# Macropad_v19.net
KiCad netlist of a schematic drawn in EAGLE
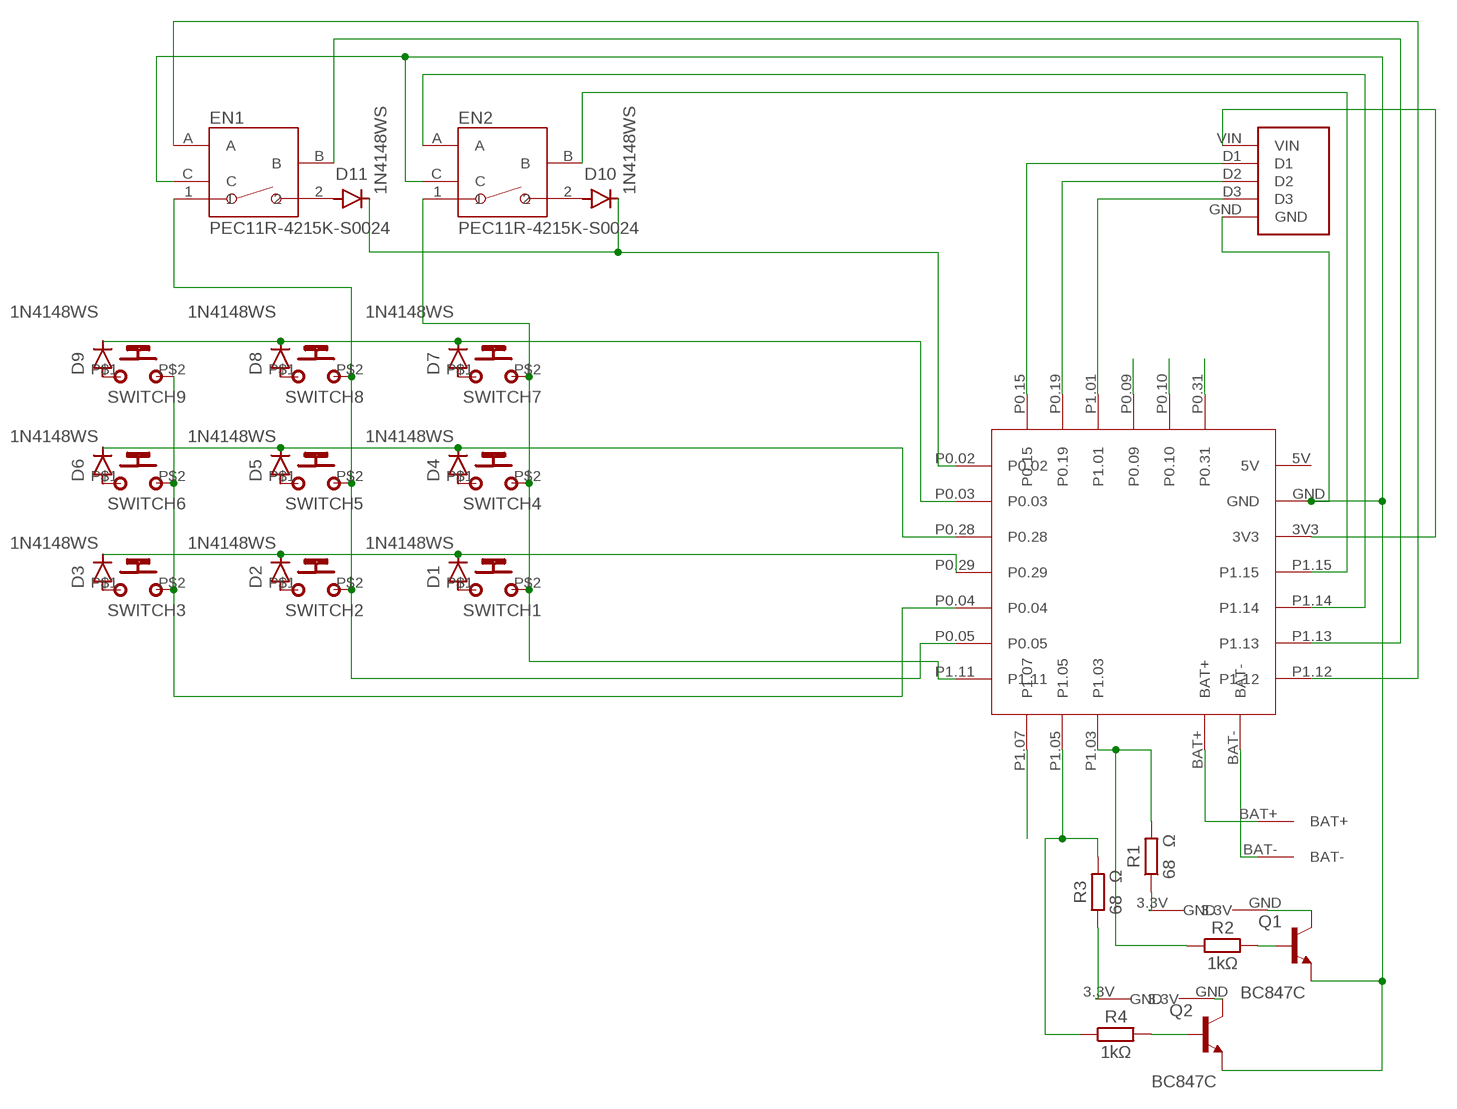
[diagram p0: schematic, sheet 1]

(export (version "E")
  (design (tool "Eeschema 10.0.6"))
  (components
    (comp (ref "D1")
      (value "1N4148WS")
      (footprint "eagle-import:SOD-323")
      (fields
        (field (name "DIGIKEY_PART_NUMBER") "1N4148WSFSTR-ND")
        (field (name "MANUFACTURER") "Diodes Incorporated")
        (field (name "CREATED_BY") "PCBLayout.com")
      )
      (libsource (lib "eagle-import") (part "1N4148WS"))
    )
    (comp (ref "D2")
      (value "1N4148WS")
      (footprint "eagle-import:SOD-323")
      (fields
        (field (name "DIGIKEY_PART_NUMBER") "1N4148WSFSTR-ND")
        (field (name "MANUFACTURER") "Diodes Incorporated")
        (field (name "CREATED_BY") "PCBLayout.com")
      )
      (libsource (lib "eagle-import") (part "1N4148WS"))
    )
    (comp (ref "D3")
      (value "1N4148WS")
      (footprint "eagle-import:SOD-323")
      (fields
        (field (name "DIGIKEY_PART_NUMBER") "1N4148WSFSTR-ND")
        (field (name "MANUFACTURER") "Diodes Incorporated")
        (field (name "CREATED_BY") "PCBLayout.com")
      )
      (libsource (lib "eagle-import") (part "1N4148WS"))
    )
    (comp (ref "D4")
      (value "1N4148WS")
      (footprint "eagle-import:SOD-323")
      (fields
        (field (name "DIGIKEY_PART_NUMBER") "1N4148WSFSTR-ND")
        (field (name "MANUFACTURER") "Diodes Incorporated")
        (field (name "CREATED_BY") "PCBLayout.com")
      )
      (libsource (lib "eagle-import") (part "1N4148WS"))
    )
    (comp (ref "D5")
      (value "1N4148WS")
      (footprint "eagle-import:SOD-323")
      (fields
        (field (name "DIGIKEY_PART_NUMBER") "1N4148WSFSTR-ND")
        (field (name "MANUFACTURER") "Diodes Incorporated")
        (field (name "CREATED_BY") "PCBLayout.com")
      )
      (libsource (lib "eagle-import") (part "1N4148WS"))
    )
    (comp (ref "D6")
      (value "1N4148WS")
      (footprint "eagle-import:SOD-323")
      (fields
        (field (name "DIGIKEY_PART_NUMBER") "1N4148WSFSTR-ND")
        (field (name "MANUFACTURER") "Diodes Incorporated")
        (field (name "CREATED_BY") "PCBLayout.com")
      )
      (libsource (lib "eagle-import") (part "1N4148WS"))
    )
    (comp (ref "D7")
      (value "1N4148WS")
      (footprint "eagle-import:SOD-323")
      (fields
        (field (name "DIGIKEY_PART_NUMBER") "1N4148WSFSTR-ND")
        (field (name "MANUFACTURER") "Diodes Incorporated")
        (field (name "CREATED_BY") "PCBLayout.com")
      )
      (libsource (lib "eagle-import") (part "1N4148WS"))
    )
    (comp (ref "D8")
      (value "1N4148WS")
      (footprint "eagle-import:SOD-323")
      (fields
        (field (name "DIGIKEY_PART_NUMBER") "1N4148WSFSTR-ND")
        (field (name "MANUFACTURER") "Diodes Incorporated")
        (field (name "CREATED_BY") "PCBLayout.com")
      )
      (libsource (lib "eagle-import") (part "1N4148WS"))
    )
    (comp (ref "D9")
      (value "1N4148WS")
      (footprint "eagle-import:SOD-323")
      (fields
        (field (name "DIGIKEY_PART_NUMBER") "1N4148WSFSTR-ND")
        (field (name "MANUFACTURER") "Diodes Incorporated")
        (field (name "CREATED_BY") "PCBLayout.com")
      )
      (libsource (lib "eagle-import") (part "1N4148WS"))
    )
    (comp (ref "D10")
      (value "1N4148WS")
      (footprint "eagle-import:SOD-323")
      (fields
        (field (name "DIGIKEY_PART_NUMBER") "1N4148WSFSTR-ND")
        (field (name "MANUFACTURER") "Diodes Incorporated")
        (field (name "CREATED_BY") "PCBLayout.com")
      )
      (libsource (lib "eagle-import") (part "1N4148WS"))
    )
    (comp (ref "D11")
      (value "1N4148WS")
      (footprint "eagle-import:SOD-323")
      (fields
        (field (name "DIGIKEY_PART_NUMBER") "1N4148WSFSTR-ND")
        (field (name "MANUFACTURER") "Diodes Incorporated")
        (field (name "CREATED_BY") "PCBLayout.com")
      )
      (libsource (lib "eagle-import") (part "1N4148WS"))
    )
    (comp (ref "EN1")
      (value "PEC11R-4215K-S0024")
      (footprint "eagle-import:PEC11R-4215K-S0024")
      (fields
        (field (name "DIGIKEY_PARTNO") "PEC11R-4215K-S0024-ND")
        (field (name "MANUFACTURER") "Bourns Inc.")
        (field (name "CREATED_BY") "PCBLayout.com")
      )
      (libsource (lib "eagle-import") (part "PEC11R-4215K-S0024"))
    )
    (comp (ref "EN2")
      (value "PEC11R-4215K-S0024")
      (footprint "eagle-import:PEC11R-4215K-S0024")
      (fields
        (field (name "DIGIKEY_PARTNO") "PEC11R-4215K-S0024-ND")
        (field (name "MANUFACTURER") "Bourns Inc.")
        (field (name "CREATED_BY") "PCBLayout.com")
      )
      (libsource (lib "eagle-import") (part "PEC11R-4215K-S0024"))
    )
    (comp (ref "Q1")
      (value "BC847C")
      (footprint "eagle-import:TRANS_BC847C")
      (fields (field (name "MF") "Diotec Semiconductor"))
      (libsource (lib "eagle-import") (part "BC847C"))
    )
    (comp (ref "Q2")
      (value "BC847C")
      (footprint "eagle-import:TRANS_BC847C")
      (fields (field (name "MF") "Diotec Semiconductor"))
      (libsource (lib "eagle-import") (part "BC847C"))
    )
    (comp (ref "R1")
      (value "68 Ω")
      (footprint "eagle-import:RESC1005X40")
      (libsource (lib "eagle-import") (part "RCHIP-0402(1005-METRIC)_"))
    )
    (comp (ref "R2")
      (value "1kΩ")
      (footprint "eagle-import:RESC1005X40")
      (libsource (lib "eagle-import") (part "RCHIP-0402(1005-METRIC)_"))
    )
    (comp (ref "R3")
      (value "68 Ω")
      (footprint "eagle-import:RESC1005X40")
      (libsource (lib "eagle-import") (part "RCHIP-0402(1005-METRIC)_"))
    )
    (comp (ref "R4")
      (value "1kΩ")
      (footprint "eagle-import:RESC1005X40")
      (libsource (lib "eagle-import") (part "RCHIP-0402(1005-METRIC)_"))
    )
    (comp (ref "SWITCH1")
      (value "MX1A-11NN")
      (footprint "eagle-import:CHERRY_MX1A-11NN_SWITCH")
      (fields (field (name "MF") "Cherry") (field (name "MP") "MX1A11NN"))
      (libsource (lib "eagle-import") (part "MX1A-11NN"))
    )
    (comp (ref "SWITCH2")
      (value "MX1A-11NN")
      (footprint "eagle-import:CHERRY_MX1A-11NN_SWITCH")
      (fields (field (name "MF") "Cherry") (field (name "MP") "MX1A11NN"))
      (libsource (lib "eagle-import") (part "MX1A-11NN"))
    )
    (comp (ref "SWITCH3")
      (value "MX1A-11NN")
      (footprint "eagle-import:CHERRY_MX1A-11NN_SWITCH")
      (fields (field (name "MF") "Cherry") (field (name "MP") "MX1A11NN"))
      (libsource (lib "eagle-import") (part "MX1A-11NN"))
    )
    (comp (ref "SWITCH4")
      (value "MX1A-11NN")
      (footprint "eagle-import:CHERRY_MX1A-11NN_SWITCH")
      (fields (field (name "MF") "Cherry") (field (name "MP") "MX1A11NN"))
      (libsource (lib "eagle-import") (part "MX1A-11NN"))
    )
    (comp (ref "SWITCH5")
      (value "MX1A-11NN")
      (footprint "eagle-import:CHERRY_MX1A-11NN_SWITCH")
      (fields (field (name "MF") "Cherry") (field (name "MP") "MX1A11NN"))
      (libsource (lib "eagle-import") (part "MX1A-11NN"))
    )
    (comp (ref "SWITCH6")
      (value "MX1A-11NN")
      (footprint "eagle-import:CHERRY_MX1A-11NN_SWITCH")
      (fields (field (name "MF") "Cherry") (field (name "MP") "MX1A11NN"))
      (libsource (lib "eagle-import") (part "MX1A-11NN"))
    )
    (comp (ref "SWITCH7")
      (value "MX1A-11NN")
      (footprint "eagle-import:CHERRY_MX1A-11NN_SWITCH")
      (fields (field (name "MF") "Cherry") (field (name "MP") "MX1A11NN"))
      (libsource (lib "eagle-import") (part "MX1A-11NN"))
    )
    (comp (ref "SWITCH8")
      (value "MX1A-11NN")
      (footprint "eagle-import:CHERRY_MX1A-11NN_SWITCH")
      (fields (field (name "MF") "Cherry") (field (name "MP") "MX1A11NN"))
      (libsource (lib "eagle-import") (part "MX1A-11NN"))
    )
    (comp (ref "SWITCH9")
      (value "MX1A-11NN")
      (footprint "eagle-import:CHERRY_MX1A-11NN_SWITCH")
      (fields (field (name "MF") "Cherry") (field (name "MP") "MX1A11NN"))
      (libsource (lib "eagle-import") (part "MX1A-11NN"))
    )
    (comp (ref "U$1")
      (value "JST-PH2.0MM")
      (footprint "eagle-import:JST-PH2.0MM")
      (libsource (lib "eagle-import") (part "JST-PH2.0MM"))
    )
    (comp (ref "U$2")
      (value "5-PIN-POGO-CONNECTOR")
      (footprint "eagle-import:5-PIN-THROUGHHOLE")
      (libsource (lib "eagle-import") (part "5-PIN-POGO-CONNECTOR"))
    )
    (comp (ref "U$3")
      (value "LED-THROUGHHOLE")
      (footprint "eagle-import:LED")
      (libsource (lib "eagle-import") (part "LED-THROUGHHOLE"))
    )
    (comp (ref "U$4")
      (value "LED-THROUGHHOLE")
      (footprint "eagle-import:LED")
      (libsource (lib "eagle-import") (part "LED-THROUGHHOLE"))
    )
    (comp (ref "XIAO_NRF52840_PLUS1")
      (value "XIAO_NRF52840_PLUS")
      (footprint "eagle-import:XIAO-NRF52840-PLUS-SMD")
      (libsource (lib "eagle-import") (part "XIAO_NRF52840_PLUS"))
    )
  )
  (nets
    (net (code "1") (name "/5V") (class "Default")
      (node (ref "XIAO_NRF52840_PLUS1") (pin "5V") (pinfunction "5V_5V") (pintype "power_in"))
    )
    (net (code "2") (name "Net-(D1-PadC)") (class "Default")
      (node (ref "D1") (pin "C") (pinfunction "C_C") (pintype "passive"))
      (node (ref "D2") (pin "C") (pinfunction "C_C") (pintype "passive"))
      (node (ref "D3") (pin "C") (pinfunction "C_C") (pintype "passive"))
      (node (ref "XIAO_NRF52840_PLUS1") (pin "P0.29") (pinfunction "P0.29_P0.29") (pintype "bidirectional"))
    )
    (net (code "3") (name "Net-(D4-PadC)") (class "Default")
      (node (ref "D4") (pin "C") (pinfunction "C_C") (pintype "passive"))
      (node (ref "D5") (pin "C") (pinfunction "C_C") (pintype "passive"))
      (node (ref "D6") (pin "C") (pinfunction "C_C") (pintype "passive"))
      (node (ref "XIAO_NRF52840_PLUS1") (pin "P0.28") (pinfunction "P0.28_P0.28") (pintype "bidirectional"))
    )
    (net (code "4") (name "Net-(D7-PadC)") (class "Default")
      (node (ref "D7") (pin "C") (pinfunction "C_C") (pintype "passive"))
      (node (ref "D8") (pin "C") (pinfunction "C_C") (pintype "passive"))
      (node (ref "D9") (pin "C") (pinfunction "C_C") (pintype "passive"))
      (node (ref "XIAO_NRF52840_PLUS1") (pin "P0.03") (pinfunction "P0.03_P0.03") (pintype "bidirectional"))
    )
    (net (code "5") (name "Net-(D10-PadA)") (class "Default")
      (node (ref "D10") (pin "A") (pinfunction "A_A") (pintype "passive"))
      (node (ref "EN2") (pin "2") (pinfunction "2_2") (pintype "passive"))
    )
    (net (code "6") (name "Net-(D10-PadC)") (class "Default")
      (node (ref "D10") (pin "C") (pinfunction "C_C") (pintype "passive"))
      (node (ref "D11") (pin "C") (pinfunction "C_C") (pintype "passive"))
      (node (ref "XIAO_NRF52840_PLUS1") (pin "P0.02") (pinfunction "P0.02_P0.02") (pintype "bidirectional"))
    )
    (net (code "7") (name "Net-(D11-PadA)") (class "Default")
      (node (ref "D11") (pin "A") (pinfunction "A_A") (pintype "passive"))
      (node (ref "EN1") (pin "2") (pinfunction "2_2") (pintype "passive"))
    )
    (net (code "8") (name "Net-(EN1-PadA)") (class "Default")
      (node (ref "EN1") (pin "A") (pinfunction "A_A") (pintype "passive"))
      (node (ref "XIAO_NRF52840_PLUS1") (pin "P1.12") (pinfunction "P1.12_P1.12") (pintype "bidirectional"))
    )
    (net (code "9") (name "Net-(EN1-PadB)") (class "Default")
      (node (ref "EN1") (pin "B") (pinfunction "B_B") (pintype "passive"))
      (node (ref "XIAO_NRF52840_PLUS1") (pin "P1.13") (pinfunction "P1.13_P1.13") (pintype "bidirectional"))
    )
    (net (code "10") (name "Net-(EN2-PadA)") (class "Default")
      (node (ref "EN2") (pin "A") (pinfunction "A_A") (pintype "passive"))
      (node (ref "XIAO_NRF52840_PLUS1") (pin "P1.14") (pinfunction "P1.14_P1.14") (pintype "bidirectional"))
    )
    (net (code "11") (name "Net-(EN2-PadB)") (class "Default")
      (node (ref "EN2") (pin "B") (pinfunction "B_B") (pintype "passive"))
      (node (ref "XIAO_NRF52840_PLUS1") (pin "P1.15") (pinfunction "P1.15_P1.15") (pintype "bidirectional"))
    )
    (net (code "12") (name "Net-(Q1-B)") (class "Default")
      (node (ref "Q1") (pin "1") (pinfunction "B_1") (pintype "passive"))
      (node (ref "R2") (pin "2") (pinfunction "2_2") (pintype "passive"))
    )
    (net (code "13") (name "Net-(Q1-C)") (class "Default")
      (node (ref "Q1") (pin "3") (pinfunction "C_3") (pintype "passive"))
      (node (ref "U$3") (pin "GND") (pinfunction "GND_GND") (pintype "power_in"))
    )
    (net (code "14") (name "Net-(Q1-E)") (class "Default")
      (node (ref "EN1") (pin "C") (pinfunction "C_C") (pintype "passive"))
      (node (ref "EN2") (pin "C") (pinfunction "C_C") (pintype "passive"))
      (node (ref "Q1") (pin "2") (pinfunction "E_2") (pintype "passive"))
      (node (ref "Q2") (pin "2") (pinfunction "E_2") (pintype "passive"))
      (node (ref "U$2") (pin "GND") (pinfunction "GND_GND") (pintype "power_in"))
      (node (ref "XIAO_NRF52840_PLUS1") (pin "GND") (pinfunction "GND_GND") (pintype "power_in"))
    )
    (net (code "15") (name "Net-(Q2-B)") (class "Default")
      (node (ref "Q2") (pin "1") (pinfunction "B_1") (pintype "passive"))
      (node (ref "R4") (pin "2") (pinfunction "2_2") (pintype "passive"))
    )
    (net (code "16") (name "Net-(Q2-C)") (class "Default")
      (node (ref "Q2") (pin "3") (pinfunction "C_3") (pintype "passive"))
      (node (ref "U$4") (pin "GND") (pinfunction "GND_GND") (pintype "power_in"))
    )
    (net (code "17") (name "Net-(R1-Pad1)") (class "Default")
      (node (ref "R1") (pin "1") (pinfunction "1_1") (pintype "passive"))
      (node (ref "U$3") (pin "3.3V") (pinfunction "3.3V_3.3V") (pintype "power_in"))
    )
    (net (code "18") (name "Net-(R1-Pad2)") (class "Default")
      (node (ref "R1") (pin "2") (pinfunction "2_2") (pintype "passive"))
      (node (ref "R2") (pin "1") (pinfunction "1_1") (pintype "passive"))
      (node (ref "XIAO_NRF52840_PLUS1") (pin "P1.03") (pinfunction "P1.03_P1.03") (pintype "bidirectional"))
    )
    (net (code "19") (name "Net-(R3-Pad1)") (class "Default")
      (node (ref "R3") (pin "1") (pinfunction "1_1") (pintype "passive"))
      (node (ref "U$4") (pin "3.3V") (pinfunction "3.3V_3.3V") (pintype "power_in"))
    )
    (net (code "20") (name "Net-(R3-Pad2)") (class "Default")
      (node (ref "R3") (pin "2") (pinfunction "2_2") (pintype "passive"))
      (node (ref "R4") (pin "1") (pinfunction "1_1") (pintype "passive"))
      (node (ref "XIAO_NRF52840_PLUS1") (pin "P1.05") (pinfunction "P1.05_P1.05") (pintype "bidirectional"))
    )
    (net (code "21") (name "Net-(SWITCH1-P)") (class "Default")
      (node (ref "D1") (pin "A") (pinfunction "A_A") (pintype "passive"))
      (node (ref "SWITCH1") (pin "P$1") (pinfunction "P_P$1") (pintype "passive"))
    )
    (net (code "22") (name "Net-(SWITCH1-S)") (class "Default")
      (node (ref "EN2") (pin "1") (pinfunction "1_1") (pintype "passive"))
      (node (ref "SWITCH1") (pin "P$2") (pinfunction "S_P$2") (pintype "passive"))
      (node (ref "SWITCH4") (pin "P$2") (pinfunction "S_P$2") (pintype "passive"))
      (node (ref "SWITCH7") (pin "P$2") (pinfunction "S_P$2") (pintype "passive"))
      (node (ref "XIAO_NRF52840_PLUS1") (pin "P1.11") (pinfunction "P1.11_P1.11") (pintype "bidirectional"))
    )
    (net (code "23") (name "Net-(SWITCH2-P)") (class "Default")
      (node (ref "D2") (pin "A") (pinfunction "A_A") (pintype "passive"))
      (node (ref "SWITCH2") (pin "P$1") (pinfunction "P_P$1") (pintype "passive"))
    )
    (net (code "24") (name "Net-(SWITCH2-S)") (class "Default")
      (node (ref "EN1") (pin "1") (pinfunction "1_1") (pintype "passive"))
      (node (ref "SWITCH2") (pin "P$2") (pinfunction "S_P$2") (pintype "passive"))
      (node (ref "SWITCH5") (pin "P$2") (pinfunction "S_P$2") (pintype "passive"))
      (node (ref "SWITCH8") (pin "P$2") (pinfunction "S_P$2") (pintype "passive"))
      (node (ref "XIAO_NRF52840_PLUS1") (pin "P0.05") (pinfunction "P0.05_P0.05") (pintype "bidirectional"))
    )
    (net (code "25") (name "Net-(SWITCH3-P)") (class "Default")
      (node (ref "D3") (pin "A") (pinfunction "A_A") (pintype "passive"))
      (node (ref "SWITCH3") (pin "P$1") (pinfunction "P_P$1") (pintype "passive"))
    )
    (net (code "26") (name "Net-(SWITCH3-S)") (class "Default")
      (node (ref "SWITCH3") (pin "P$2") (pinfunction "S_P$2") (pintype "passive"))
      (node (ref "SWITCH6") (pin "P$2") (pinfunction "S_P$2") (pintype "passive"))
      (node (ref "SWITCH9") (pin "P$2") (pinfunction "S_P$2") (pintype "passive"))
      (node (ref "XIAO_NRF52840_PLUS1") (pin "P0.04") (pinfunction "P0.04_P0.04") (pintype "bidirectional"))
    )
    (net (code "27") (name "Net-(SWITCH4-P)") (class "Default")
      (node (ref "D4") (pin "A") (pinfunction "A_A") (pintype "passive"))
      (node (ref "SWITCH4") (pin "P$1") (pinfunction "P_P$1") (pintype "passive"))
    )
    (net (code "28") (name "Net-(SWITCH5-P)") (class "Default")
      (node (ref "D5") (pin "A") (pinfunction "A_A") (pintype "passive"))
      (node (ref "SWITCH5") (pin "P$1") (pinfunction "P_P$1") (pintype "passive"))
    )
    (net (code "29") (name "Net-(SWITCH6-P)") (class "Default")
      (node (ref "D6") (pin "A") (pinfunction "A_A") (pintype "passive"))
      (node (ref "SWITCH6") (pin "P$1") (pinfunction "P_P$1") (pintype "passive"))
    )
    (net (code "30") (name "Net-(SWITCH7-P)") (class "Default")
      (node (ref "D7") (pin "A") (pinfunction "A_A") (pintype "passive"))
      (node (ref "SWITCH7") (pin "P$1") (pinfunction "P_P$1") (pintype "passive"))
    )
    (net (code "31") (name "Net-(SWITCH8-P)") (class "Default")
      (node (ref "D8") (pin "A") (pinfunction "A_A") (pintype "passive"))
      (node (ref "SWITCH8") (pin "P$1") (pinfunction "P_P$1") (pintype "passive"))
    )
    (net (code "32") (name "Net-(SWITCH9-P)") (class "Default")
      (node (ref "D9") (pin "A") (pinfunction "A_A") (pintype "passive"))
      (node (ref "SWITCH9") (pin "P$1") (pinfunction "P_P$1") (pintype "passive"))
    )
    (net (code "33") (name "Net-(U$1-PadBAT+)") (class "Default")
      (node (ref "U$1") (pin "BAT+") (pinfunction "BAT+_BAT+") (pintype "power_in"))
      (node (ref "XIAO_NRF52840_PLUS1") (pin "BAT+") (pinfunction "BAT+_BAT+") (pintype "power_in"))
    )
    (net (code "34") (name "Net-(U$1-PadBAT-)") (class "Default")
      (node (ref "U$1") (pin "BAT-") (pinfunction "BAT-_BAT-") (pintype "power_in"))
      (node (ref "XIAO_NRF52840_PLUS1") (pin "BAT-") (pinfunction "BAT-_BAT-") (pintype "power_in"))
    )
    (net (code "35") (name "Net-(U$2-PadD1)") (class "Default")
      (node (ref "U$2") (pin "D1") (pinfunction "D1_D1") (pintype "bidirectional"))
      (node (ref "XIAO_NRF52840_PLUS1") (pin "P0.15") (pinfunction "P0.15_P0.15") (pintype "bidirectional"))
    )
    (net (code "36") (name "Net-(U$2-PadD2)") (class "Default")
      (node (ref "U$2") (pin "D2") (pinfunction "D2_D2") (pintype "bidirectional"))
      (node (ref "XIAO_NRF52840_PLUS1") (pin "P0.19") (pinfunction "P0.19_P0.19") (pintype "bidirectional"))
    )
    (net (code "37") (name "Net-(U$2-PadD3)") (class "Default")
      (node (ref "U$2") (pin "D3") (pinfunction "D3_D3") (pintype "bidirectional"))
      (node (ref "XIAO_NRF52840_PLUS1") (pin "P1.01") (pinfunction "P1.01_P1.01") (pintype "bidirectional"))
    )
    (net (code "38") (name "Net-(U$2-PadVIN)") (class "Default")
      (node (ref "U$2") (pin "VIN") (pinfunction "VIN_VIN") (pintype "power_in"))
      (node (ref "XIAO_NRF52840_PLUS1") (pin "3V3") (pinfunction "3V3_3V3") (pintype "power_in"))
    )
    (net (code "39") (name "unconnected-(XIAO_NRF52840_PLUS1-PadP0.09)") (class "Default")
      (node (ref "XIAO_NRF52840_PLUS1") (pin "P0.09") (pinfunction "P0.09_P0.09") (pintype "bidirectional"))
    )
    (net (code "40") (name "unconnected-(XIAO_NRF52840_PLUS1-PadP0.10)") (class "Default")
      (node (ref "XIAO_NRF52840_PLUS1") (pin "P0.10") (pinfunction "P0.10_P0.10") (pintype "bidirectional"))
    )
    (net (code "41") (name "unconnected-(XIAO_NRF52840_PLUS1-PadP0.31)") (class "Default")
      (node (ref "XIAO_NRF52840_PLUS1") (pin "P0.31") (pinfunction "P0.31_P0.31") (pintype "bidirectional"))
    )
    (net (code "42") (name "unconnected-(XIAO_NRF52840_PLUS1-PadP1.07)") (class "Default")
      (node (ref "XIAO_NRF52840_PLUS1") (pin "P1.07") (pinfunction "P1.07_P1.07") (pintype "bidirectional"))
    )
  )
)
